# GroundsCoupling.net
KiCad netlist of a schematic drawn in Altium Designer
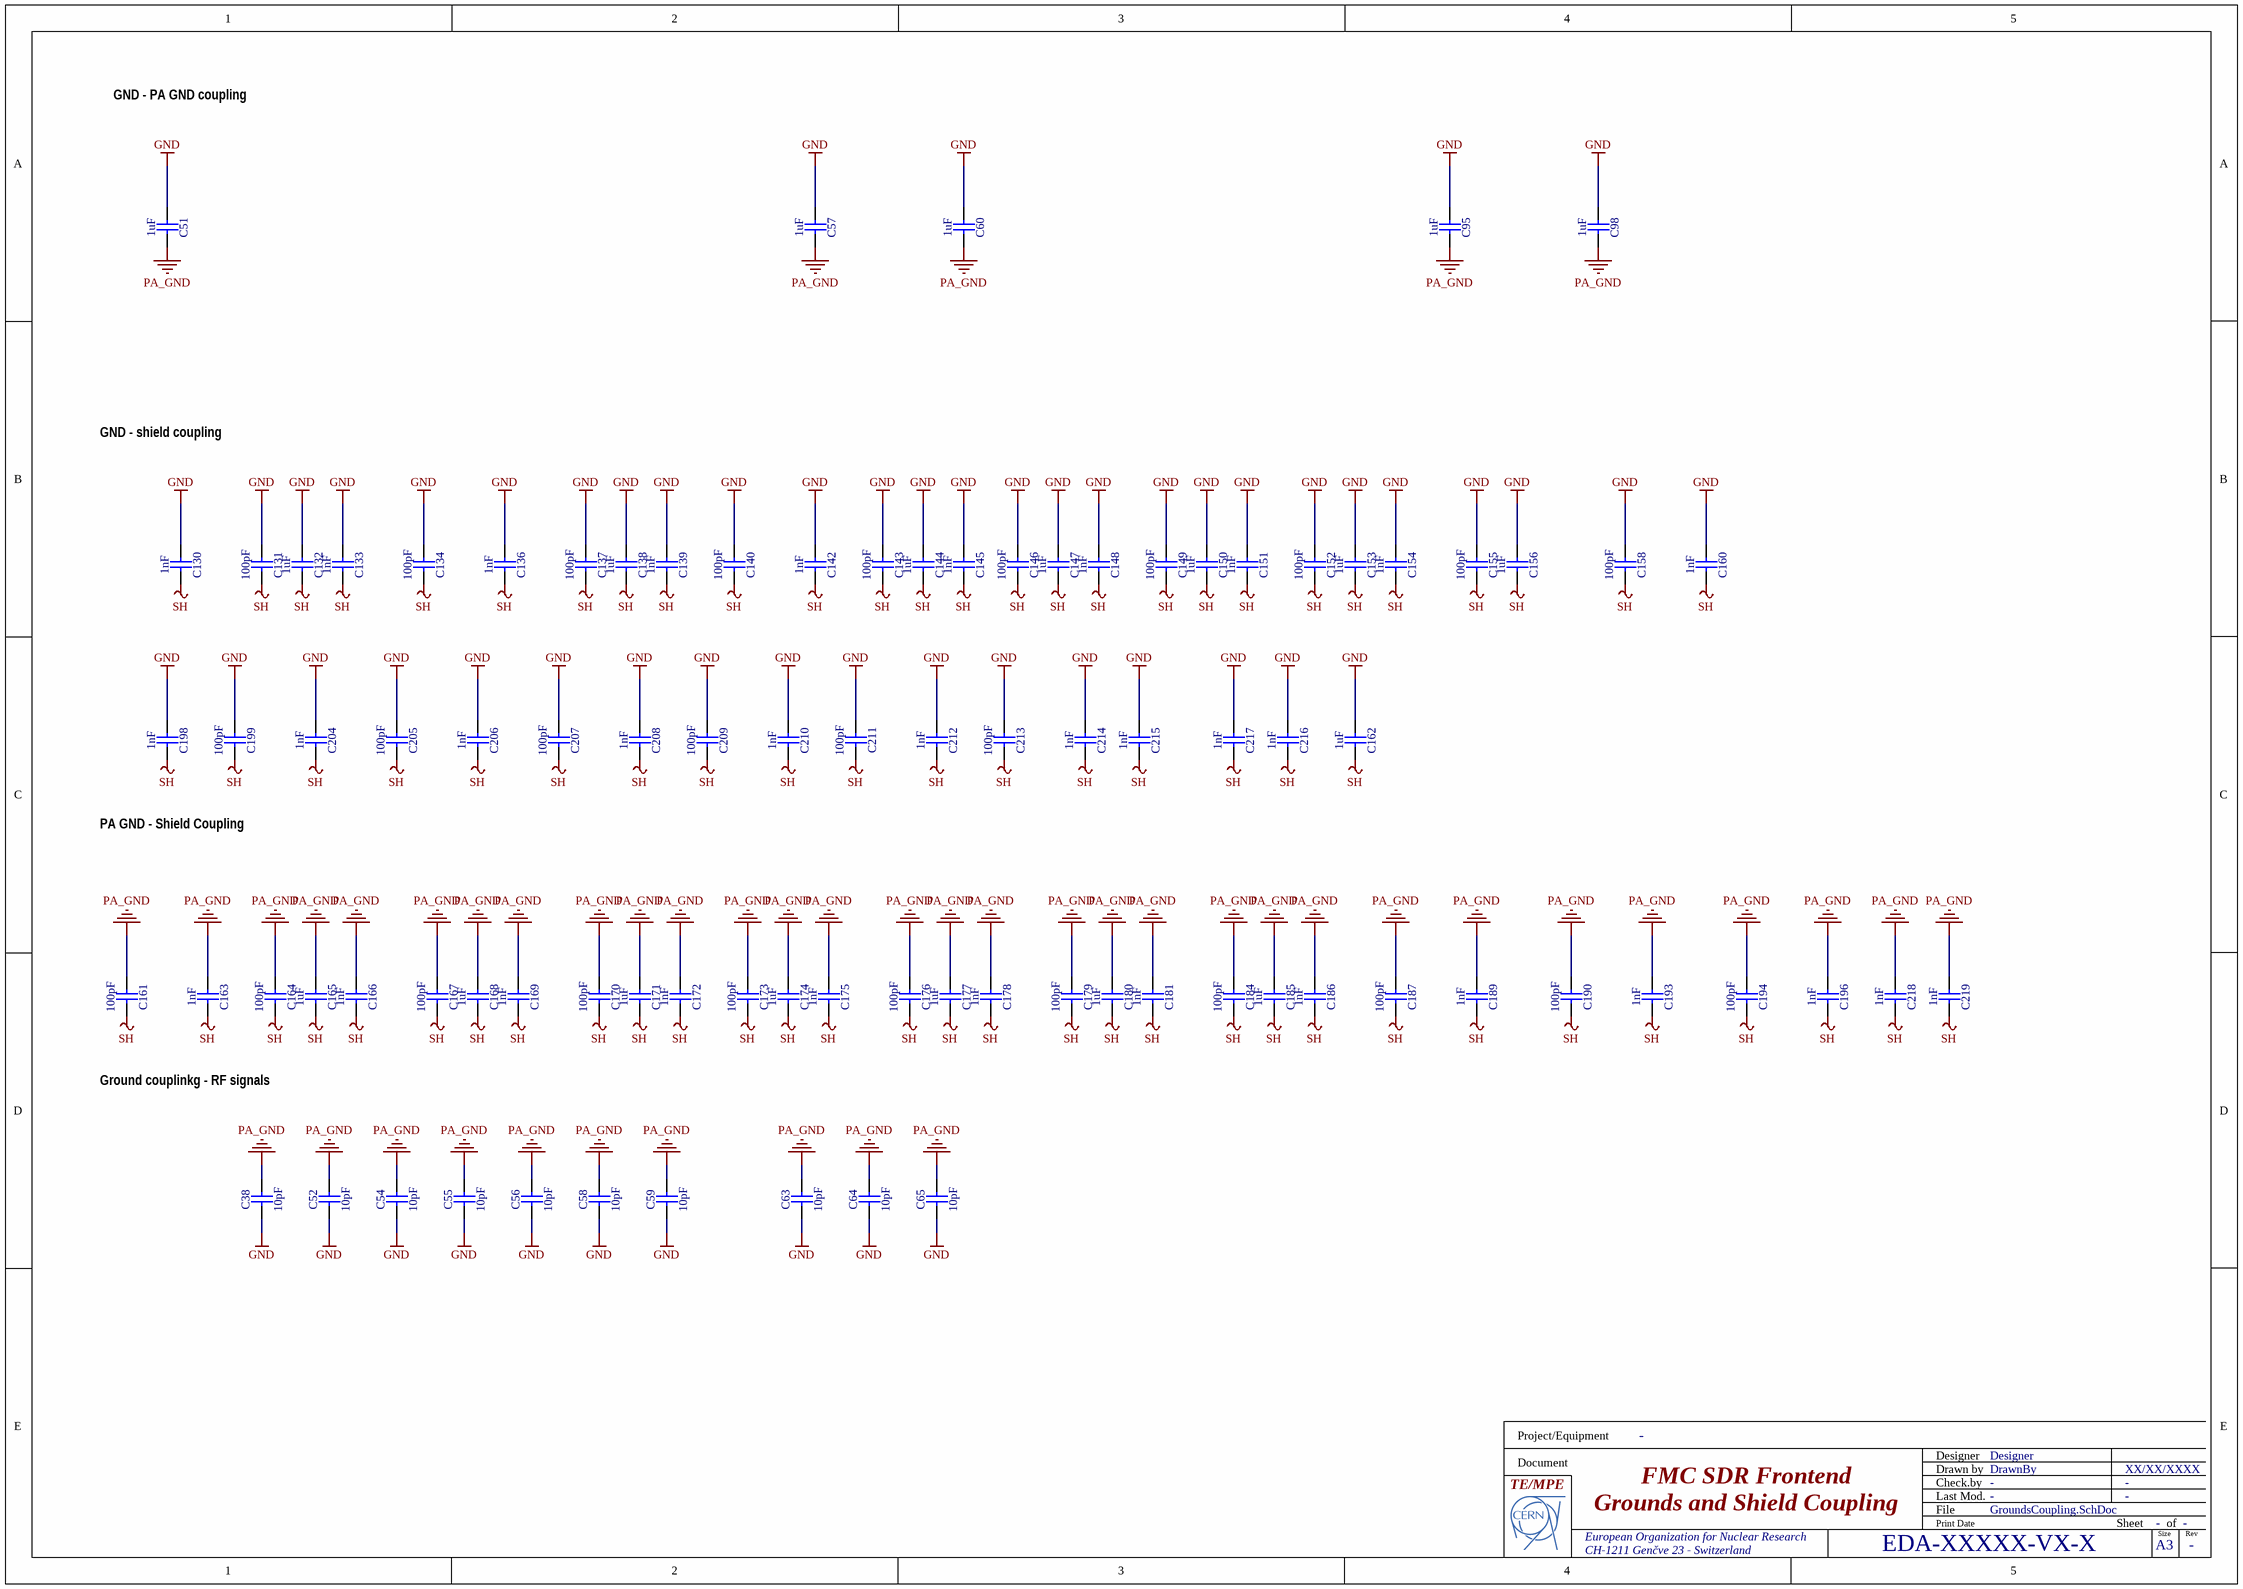
[diagram p0: GroundsCoupling.SchDoc]

(export (version "E")
  (design (tool "Eeschema 10.0.6"))
  (components
    (comp (ref "C38")
      (value "10pF")
      (footprint "CAPC1005X55N")
      (description "Non-polarised capacitor")
      (fields
        (field (name "PART NUMBER") "CC0402_10PF_50V_0.5PF_C0G_YUDEN_UMK105CG100DVHF")
        (field (name "VOLTAGE") "50V")
        (field (name "AUTHOR") "CERN DEM JLC")
      )
      (libsource (lib "Capacitors") (part "Capacitor - non polarized"))
    )
    (comp (ref "C51")
      (value "1uF")
      (footprint "CAPC3216X140N")
      (description "Non-polarised capacitor")
      (fields
        (field (name "PART NUMBER") "CC1206_1UF_50V_10%_X7R")
        (field (name "VOLTAGE") "50V")
        (field (name "AUTHOR") "CERN DEM JLC")
      )
      (libsource (lib "Capacitors") (part "Capacitor - non polarized"))
    )
    (comp (ref "C52")
      (value "10pF")
      (footprint "CAPC1005X55N")
      (description "Non-polarised capacitor")
      (fields
        (field (name "PART NUMBER") "CC0402_10PF_50V_0.5PF_C0G_YUDEN_UMK105CG100DVHF")
        (field (name "VOLTAGE") "50V")
        (field (name "AUTHOR") "CERN DEM JLC")
      )
      (libsource (lib "Capacitors") (part "Capacitor - non polarized"))
    )
    (comp (ref "C54")
      (value "10pF")
      (footprint "CAPC1005X55N")
      (description "Non-polarised capacitor")
      (fields
        (field (name "PART NUMBER") "CC0402_10PF_50V_0.5PF_C0G_YUDEN_UMK105CG100DVHF")
        (field (name "VOLTAGE") "50V")
        (field (name "AUTHOR") "CERN DEM JLC")
      )
      (libsource (lib "Capacitors") (part "Capacitor - non polarized"))
    )
    (comp (ref "C55")
      (value "10pF")
      (footprint "CAPC1005X55N")
      (description "Non-polarised capacitor")
      (fields
        (field (name "PART NUMBER") "CC0402_10PF_50V_0.5PF_C0G_YUDEN_UMK105CG100DVHF")
        (field (name "VOLTAGE") "50V")
        (field (name "AUTHOR") "CERN DEM JLC")
      )
      (libsource (lib "Capacitors") (part "Capacitor - non polarized"))
    )
    (comp (ref "C56")
      (value "10pF")
      (footprint "CAPC1005X55N")
      (description "Non-polarised capacitor")
      (fields
        (field (name "PART NUMBER") "CC0402_10PF_50V_0.5PF_C0G_YUDEN_UMK105CG100DVHF")
        (field (name "VOLTAGE") "50V")
        (field (name "AUTHOR") "CERN DEM JLC")
      )
      (libsource (lib "Capacitors") (part "Capacitor - non polarized"))
    )
    (comp (ref "C57")
      (value "1uF")
      (footprint "CAPC3216X140N")
      (description "Non-polarised capacitor")
      (fields
        (field (name "PART NUMBER") "CC1206_1UF_50V_10%_X7R")
        (field (name "VOLTAGE") "50V")
        (field (name "AUTHOR") "CERN DEM JLC")
      )
      (libsource (lib "Capacitors") (part "Capacitor - non polarized"))
    )
    (comp (ref "C58")
      (value "10pF")
      (footprint "CAPC1005X55N")
      (description "Non-polarised capacitor")
      (fields
        (field (name "PART NUMBER") "CC0402_10PF_50V_0.5PF_C0G_YUDEN_UMK105CG100DVHF")
        (field (name "VOLTAGE") "50V")
        (field (name "AUTHOR") "CERN DEM JLC")
      )
      (libsource (lib "Capacitors") (part "Capacitor - non polarized"))
    )
    (comp (ref "C59")
      (value "10pF")
      (footprint "CAPC1005X55N")
      (description "Non-polarised capacitor")
      (fields
        (field (name "PART NUMBER") "CC0402_10PF_50V_0.5PF_C0G_YUDEN_UMK105CG100DVHF")
        (field (name "VOLTAGE") "50V")
        (field (name "AUTHOR") "CERN DEM JLC")
      )
      (libsource (lib "Capacitors") (part "Capacitor - non polarized"))
    )
    (comp (ref "C60")
      (value "1uF")
      (footprint "CAPC3216X140N")
      (description "Non-polarised capacitor")
      (fields
        (field (name "PART NUMBER") "CC1206_1UF_50V_10%_X7R")
        (field (name "VOLTAGE") "50V")
        (field (name "AUTHOR") "CERN DEM JLC")
      )
      (libsource (lib "Capacitors") (part "Capacitor - non polarized"))
    )
    (comp (ref "C63")
      (value "10pF")
      (footprint "CAPC1005X55N")
      (description "Non-polarised capacitor")
      (fields
        (field (name "PART NUMBER") "CC0402_10PF_50V_0.5PF_C0G_YUDEN_UMK105CG100DVHF")
        (field (name "VOLTAGE") "50V")
        (field (name "AUTHOR") "CERN DEM JLC")
      )
      (libsource (lib "Capacitors") (part "Capacitor - non polarized"))
    )
    (comp (ref "C64")
      (value "10pF")
      (footprint "CAPC1005X55N")
      (description "Non-polarised capacitor")
      (fields
        (field (name "PART NUMBER") "CC0402_10PF_50V_0.5PF_C0G_YUDEN_UMK105CG100DVHF")
        (field (name "VOLTAGE") "50V")
        (field (name "AUTHOR") "CERN DEM JLC")
      )
      (libsource (lib "Capacitors") (part "Capacitor - non polarized"))
    )
    (comp (ref "C65")
      (value "10pF")
      (footprint "CAPC1005X55N")
      (description "Non-polarised capacitor")
      (fields
        (field (name "PART NUMBER") "CC0402_10PF_50V_0.5PF_C0G_YUDEN_UMK105CG100DVHF")
        (field (name "VOLTAGE") "50V")
        (field (name "AUTHOR") "CERN DEM JLC")
      )
      (libsource (lib "Capacitors") (part "Capacitor - non polarized"))
    )
    (comp (ref "C95")
      (value "1uF")
      (footprint "CAPC3216X140N")
      (description "Non-polarised capacitor")
      (fields
        (field (name "PART NUMBER") "CC1206_1UF_50V_10%_X7R")
        (field (name "VOLTAGE") "50V")
        (field (name "AUTHOR") "CERN DEM JLC")
      )
      (libsource (lib "Capacitors") (part "Capacitor - non polarized"))
    )
    (comp (ref "C98")
      (value "1uF")
      (footprint "CAPC3216X140N")
      (description "Non-polarised capacitor")
      (fields
        (field (name "PART NUMBER") "CC1206_1UF_50V_10%_X7R")
        (field (name "VOLTAGE") "50V")
        (field (name "AUTHOR") "CERN DEM JLC")
      )
      (libsource (lib "Capacitors") (part "Capacitor - non polarized"))
    )
    (comp (ref "C130")
      (value "1nF")
      (footprint "CAPC1005X55N")
      (description "Non-polarised capacitor")
      (fields
        (field (name "PART NUMBER") "CC0402_1NF_50V_10%_X7R")
        (field (name "VOLTAGE") "50V")
        (field (name "AUTHOR") "CERN DEM JLC")
      )
      (libsource (lib "Capacitors") (part "Capacitor - non polarized"))
    )
    (comp (ref "C131")
      (value "100pF")
      (footprint "CAPC1005X55N")
      (description "Non-polarised capacitor")
      (fields
        (field (name "PART NUMBER") "CC0402_100PF_50V_5%_C0G")
        (field (name "VOLTAGE") "50V")
        (field (name "AUTHOR") "CERN DEM JLC")
      )
      (libsource (lib "Capacitors") (part "Capacitor - non polarized"))
    )
    (comp (ref "C132")
      (value "1uF")
      (footprint "CAPC3216X140N")
      (description "Non-polarised capacitor")
      (fields
        (field (name "PART NUMBER") "CC1206_1UF_50V_10%_X7R")
        (field (name "VOLTAGE") "50V")
        (field (name "AUTHOR") "CERN DEM JLC")
      )
      (libsource (lib "Capacitors") (part "Capacitor - non polarized"))
    )
    (comp (ref "C133")
      (value "1nF")
      (footprint "CAPC1005X55N")
      (description "Non-polarised capacitor")
      (fields
        (field (name "PART NUMBER") "CC0402_1NF_50V_10%_X7R")
        (field (name "VOLTAGE") "50V")
        (field (name "AUTHOR") "CERN DEM JLC")
      )
      (libsource (lib "Capacitors") (part "Capacitor - non polarized"))
    )
    (comp (ref "C134")
      (value "100pF")
      (footprint "CAPC1005X55N")
      (description "Non-polarised capacitor")
      (fields
        (field (name "PART NUMBER") "CC0402_100PF_50V_5%_C0G")
        (field (name "VOLTAGE") "50V")
        (field (name "AUTHOR") "CERN DEM JLC")
      )
      (libsource (lib "Capacitors") (part "Capacitor - non polarized"))
    )
    (comp (ref "C136")
      (value "1nF")
      (footprint "CAPC1005X55N")
      (description "Non-polarised capacitor")
      (fields
        (field (name "PART NUMBER") "CC0402_1NF_50V_10%_X7R")
        (field (name "VOLTAGE") "50V")
        (field (name "AUTHOR") "CERN DEM JLC")
      )
      (libsource (lib "Capacitors") (part "Capacitor - non polarized"))
    )
    (comp (ref "C137")
      (value "100pF")
      (footprint "CAPC1005X55N")
      (description "Non-polarised capacitor")
      (fields
        (field (name "PART NUMBER") "CC0402_100PF_50V_5%_C0G")
        (field (name "VOLTAGE") "50V")
        (field (name "AUTHOR") "CERN DEM JLC")
      )
      (libsource (lib "Capacitors") (part "Capacitor - non polarized"))
    )
    (comp (ref "C138")
      (value "1uF")
      (footprint "CAPC3216X140N")
      (description "Non-polarised capacitor")
      (fields
        (field (name "PART NUMBER") "CC1206_1UF_50V_10%_X7R")
        (field (name "VOLTAGE") "50V")
        (field (name "AUTHOR") "CERN DEM JLC")
      )
      (libsource (lib "Capacitors") (part "Capacitor - non polarized"))
    )
    (comp (ref "C139")
      (value "1nF")
      (footprint "CAPC1005X55N")
      (description "Non-polarised capacitor")
      (fields
        (field (name "PART NUMBER") "CC0402_1NF_50V_10%_X7R")
        (field (name "VOLTAGE") "50V")
        (field (name "AUTHOR") "CERN DEM JLC")
      )
      (libsource (lib "Capacitors") (part "Capacitor - non polarized"))
    )
    (comp (ref "C140")
      (value "100pF")
      (footprint "CAPC1005X55N")
      (description "Non-polarised capacitor")
      (fields
        (field (name "PART NUMBER") "CC0402_100PF_50V_5%_C0G")
        (field (name "VOLTAGE") "50V")
        (field (name "AUTHOR") "CERN DEM JLC")
      )
      (libsource (lib "Capacitors") (part "Capacitor - non polarized"))
    )
    (comp (ref "C142")
      (value "1nF")
      (footprint "CAPC1005X55N")
      (description "Non-polarised capacitor")
      (fields
        (field (name "PART NUMBER") "CC0402_1NF_50V_10%_X7R")
        (field (name "VOLTAGE") "50V")
        (field (name "AUTHOR") "CERN DEM JLC")
      )
      (libsource (lib "Capacitors") (part "Capacitor - non polarized"))
    )
    (comp (ref "C143")
      (value "100pF")
      (footprint "CAPC1005X55N")
      (description "Non-polarised capacitor")
      (fields
        (field (name "PART NUMBER") "CC0402_100PF_50V_5%_C0G")
        (field (name "VOLTAGE") "50V")
        (field (name "AUTHOR") "CERN DEM JLC")
      )
      (libsource (lib "Capacitors") (part "Capacitor - non polarized"))
    )
    (comp (ref "C144")
      (value "1uF")
      (footprint "CAPC3216X140N")
      (description "Non-polarised capacitor")
      (fields
        (field (name "PART NUMBER") "CC1206_1UF_50V_10%_X7R")
        (field (name "VOLTAGE") "50V")
        (field (name "AUTHOR") "CERN DEM JLC")
      )
      (libsource (lib "Capacitors") (part "Capacitor - non polarized"))
    )
    (comp (ref "C145")
      (value "1nF")
      (footprint "CAPC1005X55N")
      (description "Non-polarised capacitor")
      (fields
        (field (name "PART NUMBER") "CC0402_1NF_50V_10%_X7R")
        (field (name "VOLTAGE") "50V")
        (field (name "AUTHOR") "CERN DEM JLC")
      )
      (libsource (lib "Capacitors") (part "Capacitor - non polarized"))
    )
    (comp (ref "C146")
      (value "100pF")
      (footprint "CAPC1005X55N")
      (description "Non-polarised capacitor")
      (fields
        (field (name "PART NUMBER") "CC0402_100PF_50V_5%_C0G")
        (field (name "VOLTAGE") "50V")
        (field (name "AUTHOR") "CERN DEM JLC")
      )
      (libsource (lib "Capacitors") (part "Capacitor - non polarized"))
    )
    (comp (ref "C147")
      (value "1uF")
      (footprint "CAPC3216X140N")
      (description "Non-polarised capacitor")
      (fields
        (field (name "PART NUMBER") "CC1206_1UF_50V_10%_X7R")
        (field (name "VOLTAGE") "50V")
        (field (name "AUTHOR") "CERN DEM JLC")
      )
      (libsource (lib "Capacitors") (part "Capacitor - non polarized"))
    )
    (comp (ref "C148")
      (value "1nF")
      (footprint "CAPC1005X55N")
      (description "Non-polarised capacitor")
      (fields
        (field (name "PART NUMBER") "CC0402_1NF_50V_10%_X7R")
        (field (name "VOLTAGE") "50V")
        (field (name "AUTHOR") "CERN DEM JLC")
      )
      (libsource (lib "Capacitors") (part "Capacitor - non polarized"))
    )
    (comp (ref "C149")
      (value "100pF")
      (footprint "CAPC1005X55N")
      (description "Non-polarised capacitor")
      (fields
        (field (name "PART NUMBER") "CC0402_100PF_50V_5%_C0G")
        (field (name "VOLTAGE") "50V")
        (field (name "AUTHOR") "CERN DEM JLC")
      )
      (libsource (lib "Capacitors") (part "Capacitor - non polarized"))
    )
    (comp (ref "C150")
      (value "1uF")
      (footprint "CAPC3216X140N")
      (description "Non-polarised capacitor")
      (fields
        (field (name "PART NUMBER") "CC1206_1UF_50V_10%_X7R")
        (field (name "VOLTAGE") "50V")
        (field (name "AUTHOR") "CERN DEM JLC")
      )
      (libsource (lib "Capacitors") (part "Capacitor - non polarized"))
    )
    (comp (ref "C151")
      (value "1nF")
      (footprint "CAPC1005X55N")
      (description "Non-polarised capacitor")
      (fields
        (field (name "PART NUMBER") "CC0402_1NF_50V_10%_X7R")
        (field (name "VOLTAGE") "50V")
        (field (name "AUTHOR") "CERN DEM JLC")
      )
      (libsource (lib "Capacitors") (part "Capacitor - non polarized"))
    )
    (comp (ref "C152")
      (value "100pF")
      (footprint "CAPC1005X55N")
      (description "Non-polarised capacitor")
      (fields
        (field (name "PART NUMBER") "CC0402_100PF_50V_5%_C0G")
        (field (name "VOLTAGE") "50V")
        (field (name "AUTHOR") "CERN DEM JLC")
      )
      (libsource (lib "Capacitors") (part "Capacitor - non polarized"))
    )
    (comp (ref "C153")
      (value "1uF")
      (footprint "CAPC3216X140N")
      (description "Non-polarised capacitor")
      (fields
        (field (name "PART NUMBER") "CC1206_1UF_50V_10%_X7R")
        (field (name "VOLTAGE") "50V")
        (field (name "AUTHOR") "CERN DEM JLC")
      )
      (libsource (lib "Capacitors") (part "Capacitor - non polarized"))
    )
    (comp (ref "C154")
      (value "1nF")
      (footprint "CAPC1005X55N")
      (description "Non-polarised capacitor")
      (fields
        (field (name "PART NUMBER") "CC0402_1NF_50V_10%_X7R")
        (field (name "VOLTAGE") "50V")
        (field (name "AUTHOR") "CERN DEM JLC")
      )
      (libsource (lib "Capacitors") (part "Capacitor - non polarized"))
    )
    (comp (ref "C155")
      (value "100pF")
      (footprint "CAPC1005X55N")
      (description "Non-polarised capacitor")
      (fields
        (field (name "PART NUMBER") "CC0402_100PF_50V_5%_C0G")
        (field (name "VOLTAGE") "50V")
        (field (name "AUTHOR") "CERN DEM JLC")
      )
      (libsource (lib "Capacitors") (part "Capacitor - non polarized"))
    )
    (comp (ref "C156")
      (value "1uF")
      (footprint "CAPC3216X140N")
      (description "Non-polarised capacitor")
      (fields
        (field (name "PART NUMBER") "CC1206_1UF_50V_10%_X7R")
        (field (name "VOLTAGE") "50V")
        (field (name "AUTHOR") "CERN DEM JLC")
      )
      (libsource (lib "Capacitors") (part "Capacitor - non polarized"))
    )
    (comp (ref "C158")
      (value "100pF")
      (footprint "CAPC1005X55N")
      (description "Non-polarised capacitor")
      (fields
        (field (name "PART NUMBER") "CC0402_100PF_50V_5%_C0G")
        (field (name "VOLTAGE") "50V")
        (field (name "AUTHOR") "CERN DEM JLC")
      )
      (libsource (lib "Capacitors") (part "Capacitor - non polarized"))
    )
    (comp (ref "C160")
      (value "1nF")
      (footprint "CAPC1005X55N")
      (description "Non-polarised capacitor")
      (fields
        (field (name "PART NUMBER") "CC0402_1NF_50V_10%_X7R")
        (field (name "VOLTAGE") "50V")
        (field (name "AUTHOR") "CERN DEM JLC")
      )
      (libsource (lib "Capacitors") (part "Capacitor - non polarized"))
    )
    (comp (ref "C161")
      (value "100pF")
      (footprint "CAPC1005X55N")
      (description "Non-polarised capacitor")
      (fields
        (field (name "PART NUMBER") "CC0402_100PF_50V_5%_C0G")
        (field (name "VOLTAGE") "50V")
        (field (name "AUTHOR") "CERN DEM JLC")
      )
      (libsource (lib "Capacitors") (part "Capacitor - non polarized"))
    )
    (comp (ref "C162")
      (value "1uF")
      (footprint "CAPC3216X140N")
      (description "Non-polarised capacitor")
      (fields
        (field (name "PART NUMBER") "CC1206_1UF_50V_10%_X7R")
        (field (name "VOLTAGE") "50V")
        (field (name "AUTHOR") "CERN DEM JLC")
      )
      (libsource (lib "Capacitors") (part "Capacitor - non polarized"))
    )
    (comp (ref "C163")
      (value "1nF")
      (footprint "CAPC1005X55N")
      (description "Non-polarised capacitor")
      (fields
        (field (name "PART NUMBER") "CC0402_1NF_50V_10%_X7R")
        (field (name "VOLTAGE") "50V")
        (field (name "AUTHOR") "CERN DEM JLC")
      )
      (libsource (lib "Capacitors") (part "Capacitor - non polarized"))
    )
    (comp (ref "C164")
      (value "100pF")
      (footprint "CAPC1005X55N")
      (description "Non-polarised capacitor")
      (fields
        (field (name "PART NUMBER") "CC0402_100PF_50V_5%_C0G")
        (field (name "VOLTAGE") "50V")
        (field (name "AUTHOR") "CERN DEM JLC")
      )
      (libsource (lib "Capacitors") (part "Capacitor - non polarized"))
    )
    (comp (ref "C165")
      (value "1uF")
      (footprint "CAPC3216X140N")
      (description "Non-polarised capacitor")
      (fields
        (field (name "PART NUMBER") "CC1206_1UF_50V_10%_X7R")
        (field (name "VOLTAGE") "50V")
        (field (name "AUTHOR") "CERN DEM JLC")
      )
      (libsource (lib "Capacitors") (part "Capacitor - non polarized"))
    )
    (comp (ref "C166")
      (value "1nF")
      (footprint "CAPC1005X55N")
      (description "Non-polarised capacitor")
      (fields
        (field (name "PART NUMBER") "CC0402_1NF_50V_10%_X7R")
        (field (name "VOLTAGE") "50V")
        (field (name "AUTHOR") "CERN DEM JLC")
      )
      (libsource (lib "Capacitors") (part "Capacitor - non polarized"))
    )
    (comp (ref "C167")
      (value "100pF")
      (footprint "CAPC1005X55N")
      (description "Non-polarised capacitor")
      (fields
        (field (name "PART NUMBER") "CC0402_100PF_50V_5%_C0G")
        (field (name "VOLTAGE") "50V")
        (field (name "AUTHOR") "CERN DEM JLC")
      )
      (libsource (lib "Capacitors") (part "Capacitor - non polarized"))
    )
    (comp (ref "C168")
      (value "1uF")
      (footprint "CAPC3216X140N")
      (description "Non-polarised capacitor")
      (fields
        (field (name "PART NUMBER") "CC1206_1UF_50V_10%_X7R")
        (field (name "VOLTAGE") "50V")
        (field (name "AUTHOR") "CERN DEM JLC")
      )
      (libsource (lib "Capacitors") (part "Capacitor - non polarized"))
    )
    (comp (ref "C169")
      (value "1nF")
      (footprint "CAPC1005X55N")
      (description "Non-polarised capacitor")
      (fields
        (field (name "PART NUMBER") "CC0402_1NF_50V_10%_X7R")
        (field (name "VOLTAGE") "50V")
        (field (name "AUTHOR") "CERN DEM JLC")
      )
      (libsource (lib "Capacitors") (part "Capacitor - non polarized"))
    )
    (comp (ref "C170")
      (value "100pF")
      (footprint "CAPC1005X55N")
      (description "Non-polarised capacitor")
      (fields
        (field (name "PART NUMBER") "CC0402_100PF_50V_5%_C0G")
        (field (name "VOLTAGE") "50V")
        (field (name "AUTHOR") "CERN DEM JLC")
      )
      (libsource (lib "Capacitors") (part "Capacitor - non polarized"))
    )
    (comp (ref "C171")
      (value "1uF")
      (footprint "CAPC3216X140N")
      (description "Non-polarised capacitor")
      (fields
        (field (name "PART NUMBER") "CC1206_1UF_50V_10%_X7R")
        (field (name "VOLTAGE") "50V")
        (field (name "AUTHOR") "CERN DEM JLC")
      )
      (libsource (lib "Capacitors") (part "Capacitor - non polarized"))
    )
    (comp (ref "C172")
      (value "1nF")
      (footprint "CAPC1005X55N")
      (description "Non-polarised capacitor")
      (fields
        (field (name "PART NUMBER") "CC0402_1NF_50V_10%_X7R")
        (field (name "VOLTAGE") "50V")
        (field (name "AUTHOR") "CERN DEM JLC")
      )
      (libsource (lib "Capacitors") (part "Capacitor - non polarized"))
    )
    (comp (ref "C173")
      (value "100pF")
      (footprint "CAPC1005X55N")
      (description "Non-polarised capacitor")
      (fields
        (field (name "PART NUMBER") "CC0402_100PF_50V_5%_C0G")
        (field (name "VOLTAGE") "50V")
        (field (name "AUTHOR") "CERN DEM JLC")
      )
      (libsource (lib "Capacitors") (part "Capacitor - non polarized"))
    )
    (comp (ref "C174")
      (value "1uF")
      (footprint "CAPC3216X140N")
      (description "Non-polarised capacitor")
      (fields
        (field (name "PART NUMBER") "CC1206_1UF_50V_10%_X7R")
        (field (name "VOLTAGE") "50V")
        (field (name "AUTHOR") "CERN DEM JLC")
      )
      (libsource (lib "Capacitors") (part "Capacitor - non polarized"))
    )
    (comp (ref "C175")
      (value "1nF")
      (footprint "CAPC1005X55N")
      (description "Non-polarised capacitor")
      (fields
        (field (name "PART NUMBER") "CC0402_1NF_50V_10%_X7R")
        (field (name "VOLTAGE") "50V")
        (field (name "AUTHOR") "CERN DEM JLC")
      )
      (libsource (lib "Capacitors") (part "Capacitor - non polarized"))
    )
    (comp (ref "C176")
      (value "100pF")
      (footprint "CAPC1005X55N")
      (description "Non-polarised capacitor")
      (fields
        (field (name "PART NUMBER") "CC0402_100PF_50V_5%_C0G")
        (field (name "VOLTAGE") "50V")
        (field (name "AUTHOR") "CERN DEM JLC")
      )
      (libsource (lib "Capacitors") (part "Capacitor - non polarized"))
    )
    (comp (ref "C177")
      (value "1uF")
      (footprint "CAPC3216X140N")
      (description "Non-polarised capacitor")
      (fields
        (field (name "PART NUMBER") "CC1206_1UF_50V_10%_X7R")
        (field (name "VOLTAGE") "50V")
        (field (name "AUTHOR") "CERN DEM JLC")
      )
      (libsource (lib "Capacitors") (part "Capacitor - non polarized"))
    )
    (comp (ref "C178")
      (value "1nF")
      (footprint "CAPC1005X55N")
      (description "Non-polarised capacitor")
      (fields
        (field (name "PART NUMBER") "CC0402_1NF_50V_10%_X7R")
        (field (name "VOLTAGE") "50V")
        (field (name "AUTHOR") "CERN DEM JLC")
      )
      (libsource (lib "Capacitors") (part "Capacitor - non polarized"))
    )
    (comp (ref "C179")
      (value "100pF")
      (footprint "CAPC1005X55N")
      (description "Non-polarised capacitor")
      (fields
        (field (name "PART NUMBER") "CC0402_100PF_50V_5%_C0G")
        (field (name "VOLTAGE") "50V")
        (field (name "AUTHOR") "CERN DEM JLC")
      )
      (libsource (lib "Capacitors") (part "Capacitor - non polarized"))
    )
    (comp (ref "C180")
      (value "1uF")
      (footprint "CAPC3216X140N")
      (description "Non-polarised capacitor")
      (fields
        (field (name "PART NUMBER") "CC1206_1UF_50V_10%_X7R")
        (field (name "VOLTAGE") "50V")
        (field (name "AUTHOR") "CERN DEM JLC")
      )
      (libsource (lib "Capacitors") (part "Capacitor - non polarized"))
    )
    (comp (ref "C181")
      (value "1nF")
      (footprint "CAPC1005X55N")
      (description "Non-polarised capacitor")
      (fields
        (field (name "PART NUMBER") "CC0402_1NF_50V_10%_X7R")
        (field (name "VOLTAGE") "50V")
        (field (name "AUTHOR") "CERN DEM JLC")
      )
      (libsource (lib "Capacitors") (part "Capacitor - non polarized"))
    )
    (comp (ref "C184")
      (value "100pF")
      (footprint "CAPC1005X55N")
      (description "Non-polarised capacitor")
      (fields
        (field (name "PART NUMBER") "CC0402_100PF_50V_5%_C0G")
        (field (name "VOLTAGE") "50V")
        (field (name "AUTHOR") "CERN DEM JLC")
      )
      (libsource (lib "Capacitors") (part "Capacitor - non polarized"))
    )
    (comp (ref "C185")
      (value "1uF")
      (footprint "CAPC3216X140N")
      (description "Non-polarised capacitor")
      (fields
        (field (name "PART NUMBER") "CC1206_1UF_50V_10%_X7R")
        (field (name "VOLTAGE") "50V")
        (field (name "AUTHOR") "CERN DEM JLC")
      )
      (libsource (lib "Capacitors") (part "Capacitor - non polarized"))
    )
    (comp (ref "C186")
      (value "1nF")
      (footprint "CAPC1005X55N")
      (description "Non-polarised capacitor")
      (fields
        (field (name "PART NUMBER") "CC0402_1NF_50V_10%_X7R")
        (field (name "VOLTAGE") "50V")
        (field (name "AUTHOR") "CERN DEM JLC")
      )
      (libsource (lib "Capacitors") (part "Capacitor - non polarized"))
    )
    (comp (ref "C187")
      (value "100pF")
      (footprint "CAPC1005X55N")
      (description "Non-polarised capacitor")
      (fields
        (field (name "PART NUMBER") "CC0402_100PF_50V_5%_C0G")
        (field (name "VOLTAGE") "50V")
        (field (name "AUTHOR") "CERN DEM JLC")
      )
      (libsource (lib "Capacitors") (part "Capacitor - non polarized"))
    )
    (comp (ref "C189")
      (value "1nF")
      (footprint "CAPC1005X55N")
      (description "Non-polarised capacitor")
      (fields
        (field (name "PART NUMBER") "CC0402_1NF_50V_10%_X7R")
        (field (name "VOLTAGE") "50V")
        (field (name "AUTHOR") "CERN DEM JLC")
      )
      (libsource (lib "Capacitors") (part "Capacitor - non polarized"))
    )
    (comp (ref "C190")
      (value "100pF")
      (footprint "CAPC1005X55N")
      (description "Non-polarised capacitor")
      (fields
        (field (name "PART NUMBER") "CC0402_100PF_50V_5%_C0G")
        (field (name "VOLTAGE") "50V")
        (field (name "AUTHOR") "CERN DEM JLC")
      )
      (libsource (lib "Capacitors") (part "Capacitor - non polarized"))
    )
    (comp (ref "C193")
      (value "1nF")
      (footprint "CAPC1005X55N")
      (description "Non-polarised capacitor")
      (fields
        (field (name "PART NUMBER") "CC0402_1NF_50V_10%_X7R")
        (field (name "VOLTAGE") "50V")
        (field (name "AUTHOR") "CERN DEM JLC")
      )
      (libsource (lib "Capacitors") (part "Capacitor - non polarized"))
    )
    (comp (ref "C194")
      (value "100pF")
      (footprint "CAPC1005X55N")
      (description "Non-polarised capacitor")
      (fields
        (field (name "PART NUMBER") "CC0402_100PF_50V_5%_C0G")
        (field (name "VOLTAGE") "50V")
        (field (name "AUTHOR") "CERN DEM JLC")
      )
      (libsource (lib "Capacitors") (part "Capacitor - non polarized"))
    )
    (comp (ref "C196")
      (value "1nF")
      (footprint "CAPC1005X55N")
      (description "Non-polarised capacitor")
      (fields
        (field (name "PART NUMBER") "CC0402_1NF_50V_10%_X7R")
        (field (name "VOLTAGE") "50V")
        (field (name "AUTHOR") "CERN DEM JLC")
      )
      (libsource (lib "Capacitors") (part "Capacitor - non polarized"))
    )
    (comp (ref "C198")
      (value "1nF")
      (footprint "CAPC1005X55N")
      (description "Non-polarised capacitor")
      (fields
        (field (name "PART NUMBER") "CC0402_1NF_50V_10%_X7R")
        (field (name "VOLTAGE") "50V")
        (field (name "AUTHOR") "CERN DEM JLC")
      )
      (libsource (lib "Capacitors") (part "Capacitor - non polarized"))
    )
    (comp (ref "C199")
      (value "100pF")
      (footprint "CAPC1005X55N")
      (description "Non-polarised capacitor")
      (fields
        (field (name "PART NUMBER") "CC0402_100PF_50V_5%_C0G")
        (field (name "VOLTAGE") "50V")
        (field (name "AUTHOR") "CERN DEM JLC")
      )
      (libsource (lib "Capacitors") (part "Capacitor - non polarized"))
    )
    (comp (ref "C204")
      (value "1nF")
      (footprint "CAPC1005X55N")
      (description "Non-polarised capacitor")
      (fields
        (field (name "PART NUMBER") "CC0402_1NF_50V_10%_X7R")
        (field (name "VOLTAGE") "50V")
        (field (name "AUTHOR") "CERN DEM JLC")
      )
      (libsource (lib "Capacitors") (part "Capacitor - non polarized"))
    )
    (comp (ref "C205")
      (value "100pF")
      (footprint "CAPC1005X55N")
      (description "Non-polarised capacitor")
      (fields
        (field (name "PART NUMBER") "CC0402_100PF_50V_5%_C0G")
        (field (name "VOLTAGE") "50V")
        (field (name "AUTHOR") "CERN DEM JLC")
      )
      (libsource (lib "Capacitors") (part "Capacitor - non polarized"))
    )
    (comp (ref "C206")
      (value "1nF")
      (footprint "CAPC1005X55N")
      (description "Non-polarised capacitor")
      (fields
        (field (name "PART NUMBER") "CC0402_1NF_50V_10%_X7R")
        (field (name "VOLTAGE") "50V")
        (field (name "AUTHOR") "CERN DEM JLC")
      )
      (libsource (lib "Capacitors") (part "Capacitor - non polarized"))
    )
    (comp (ref "C207")
      (value "100pF")
      (footprint "CAPC1005X55N")
      (description "Non-polarised capacitor")
      (fields
        (field (name "PART NUMBER") "CC0402_100PF_50V_5%_C0G")
        (field (name "VOLTAGE") "50V")
        (field (name "AUTHOR") "CERN DEM JLC")
      )
      (libsource (lib "Capacitors") (part "Capacitor - non polarized"))
    )
    (comp (ref "C208")
      (value "1nF")
      (footprint "CAPC1005X55N")
      (description "Non-polarised capacitor")
      (fields
        (field (name "PART NUMBER") "CC0402_1NF_50V_10%_X7R")
        (field (name "VOLTAGE") "50V")
        (field (name "AUTHOR") "CERN DEM JLC")
      )
      (libsource (lib "Capacitors") (part "Capacitor - non polarized"))
    )
    (comp (ref "C209")
      (value "100pF")
      (footprint "CAPC1005X55N")
      (description "Non-polarised capacitor")
      (fields
        (field (name "PART NUMBER") "CC0402_100PF_50V_5%_C0G")
        (field (name "VOLTAGE") "50V")
        (field (name "AUTHOR") "CERN DEM JLC")
      )
      (libsource (lib "Capacitors") (part "Capacitor - non polarized"))
    )
    (comp (ref "C210")
      (value "1nF")
      (footprint "CAPC1005X55N")
      (description "Non-polarised capacitor")
      (fields
        (field (name "PART NUMBER") "CC0402_1NF_50V_10%_X7R")
        (field (name "VOLTAGE") "50V")
        (field (name "AUTHOR") "CERN DEM JLC")
      )
      (libsource (lib "Capacitors") (part "Capacitor - non polarized"))
    )
    (comp (ref "C211")
      (value "100pF")
      (footprint "CAPC1005X55N")
      (description "Non-polarised capacitor")
      (fields
        (field (name "PART NUMBER") "CC0402_100PF_50V_5%_C0G")
        (field (name "VOLTAGE") "50V")
        (field (name "AUTHOR") "CERN DEM JLC")
      )
      (libsource (lib "Capacitors") (part "Capacitor - non polarized"))
    )
    (comp (ref "C212")
      (value "1nF")
      (footprint "CAPC1005X55N")
      (description "Non-polarised capacitor")
      (fields
        (field (name "PART NUMBER") "CC0402_1NF_50V_10%_X7R")
        (field (name "VOLTAGE") "50V")
        (field (name "AUTHOR") "CERN DEM JLC")
      )
      (libsource (lib "Capacitors") (part "Capacitor - non polarized"))
    )
    (comp (ref "C213")
      (value "100pF")
      (footprint "CAPC1005X55N")
      (description "Non-polarised capacitor")
      (fields
        (field (name "PART NUMBER") "CC0402_100PF_50V_5%_C0G")
        (field (name "VOLTAGE") "50V")
        (field (name "AUTHOR") "CERN DEM JLC")
      )
      (libsource (lib "Capacitors") (part "Capacitor - non polarized"))
    )
    (comp (ref "C214")
      (value "1nF")
      (footprint "CAPC1005X55N")
      (description "Non-polarised capacitor")
      (fields
        (field (name "PART NUMBER") "CC0402_1NF_50V_10%_X7R")
        (field (name "VOLTAGE") "50V")
        (field (name "AUTHOR") "CERN DEM JLC")
      )
      (libsource (lib "Capacitors") (part "Capacitor - non polarized"))
    )
    (comp (ref "C215")
      (value "1nF")
      (footprint "CAPC1005X55N")
      (description "Non-polarised capacitor")
      (fields
        (field (name "PART NUMBER") "CC0402_1NF_50V_10%_X7R")
        (field (name "VOLTAGE") "50V")
        (field (name "AUTHOR") "CERN DEM JLC")
      )
      (libsource (lib "Capacitors") (part "Capacitor - non polarized"))
    )
    (comp (ref "C216")
      (value "1nF")
      (footprint "CAPC1005X55N")
      (description "Non-polarised capacitor")
      (fields
        (field (name "PART NUMBER") "CC0402_1NF_50V_10%_X7R")
        (field (name "VOLTAGE") "50V")
        (field (name "AUTHOR") "CERN DEM JLC")
      )
      (libsource (lib "Capacitors") (part "Capacitor - non polarized"))
    )
    (comp (ref "C217")
      (value "1nF")
      (footprint "CAPC1005X55N")
      (description "Non-polarised capacitor")
      (fields
        (field (name "PART NUMBER") "CC0402_1NF_50V_10%_X7R")
        (field (name "VOLTAGE") "50V")
        (field (name "AUTHOR") "CERN DEM JLC")
      )
      (libsource (lib "Capacitors") (part "Capacitor - non polarized"))
    )
    (comp (ref "C218")
      (value "1nF")
      (footprint "CAPC1005X55N")
      (description "Non-polarised capacitor")
      (fields
        (field (name "PART NUMBER") "CC0402_1NF_50V_10%_X7R")
        (field (name "VOLTAGE") "50V")
        (field (name "AUTHOR") "CERN DEM JLC")
      )
      (libsource (lib "Capacitors") (part "Capacitor - non polarized"))
    )
    (comp (ref "C219")
      (value "1nF")
      (footprint "CAPC1005X55N")
      (description "Non-polarised capacitor")
      (fields
        (field (name "PART NUMBER") "CC0402_1NF_50V_10%_X7R")
        (field (name "VOLTAGE") "50V")
        (field (name "AUTHOR") "CERN DEM JLC")
      )
      (libsource (lib "Capacitors") (part "Capacitor - non polarized"))
    )
  )
  (nets
    (net (code "1") (name "GND") (class "Default")
      (node (ref "C130") (pin "1") (pinfunction "1_1") (pintype "passive"))
      (node (ref "C131") (pin "1") (pinfunction "1_1") (pintype "passive"))
      (node (ref "C132") (pin "1") (pinfunction "1_1") (pintype "passive"))
      (node (ref "C133") (pin "1") (pinfunction "1_1") (pintype "passive"))
      (node (ref "C134") (pin "1") (pinfunction "1_1") (pintype "passive"))
      (node (ref "C136") (pin "1") (pinfunction "1_1") (pintype "passive"))
      (node (ref "C137") (pin "1") (pinfunction "1_1") (pintype "passive"))
      (node (ref "C138") (pin "1") (pinfunction "1_1") (pintype "passive"))
      (node (ref "C139") (pin "1") (pinfunction "1_1") (pintype "passive"))
      (node (ref "C140") (pin "1") (pinfunction "1_1") (pintype "passive"))
      (node (ref "C142") (pin "1") (pinfunction "1_1") (pintype "passive"))
      (node (ref "C143") (pin "1") (pinfunction "1_1") (pintype "passive"))
      (node (ref "C144") (pin "1") (pinfunction "1_1") (pintype "passive"))
      (node (ref "C145") (pin "1") (pinfunction "1_1") (pintype "passive"))
      (node (ref "C146") (pin "1") (pinfunction "1_1") (pintype "passive"))
      (node (ref "C147") (pin "1") (pinfunction "1_1") (pintype "passive"))
      (node (ref "C148") (pin "1") (pinfunction "1_1") (pintype "passive"))
      (node (ref "C149") (pin "1") (pinfunction "1_1") (pintype "passive"))
      (node (ref "C150") (pin "1") (pinfunction "1_1") (pintype "passive"))
      (node (ref "C151") (pin "1") (pinfunction "1_1") (pintype "passive"))
      (node (ref "C152") (pin "1") (pinfunction "1_1") (pintype "passive"))
      (node (ref "C153") (pin "1") (pinfunction "1_1") (pintype "passive"))
      (node (ref "C154") (pin "1") (pinfunction "1_1") (pintype "passive"))
      (node (ref "C155") (pin "1") (pinfunction "1_1") (pintype "passive"))
      (node (ref "C156") (pin "1") (pinfunction "1_1") (pintype "passive"))
      (node (ref "C158") (pin "1") (pinfunction "1_1") (pintype "passive"))
      (node (ref "C160") (pin "1") (pinfunction "1_1") (pintype "passive"))
      (node (ref "C162") (pin "1") (pinfunction "1_1") (pintype "passive"))
      (node (ref "C198") (pin "1") (pinfunction "1_1") (pintype "passive"))
      (node (ref "C199") (pin "1") (pinfunction "1_1") (pintype "passive"))
      (node (ref "C204") (pin "1") (pinfunction "1_1") (pintype "passive"))
      (node (ref "C205") (pin "1") (pinfunction "1_1") (pintype "passive"))
      (node (ref "C206") (pin "1") (pinfunction "1_1") (pintype "passive"))
      (node (ref "C207") (pin "1") (pinfunction "1_1") (pintype "passive"))
      (node (ref "C208") (pin "1") (pinfunction "1_1") (pintype "passive"))
      (node (ref "C209") (pin "1") (pinfunction "1_1") (pintype "passive"))
      (node (ref "C210") (pin "1") (pinfunction "1_1") (pintype "passive"))
      (node (ref "C211") (pin "1") (pinfunction "1_1") (pintype "passive"))
      (node (ref "C212") (pin "1") (pinfunction "1_1") (pintype "passive"))
      (node (ref "C213") (pin "1") (pinfunction "1_1") (pintype "passive"))
      (node (ref "C214") (pin "1") (pinfunction "1_1") (pintype "passive"))
      (node (ref "C215") (pin "1") (pinfunction "1_1") (pintype "passive"))
      (node (ref "C216") (pin "1") (pinfunction "1_1") (pintype "passive"))
      (node (ref "C217") (pin "1") (pinfunction "1_1") (pintype "passive"))
      (node (ref "C38") (pin "1") (pinfunction "1_1") (pintype "passive"))
      (node (ref "C51") (pin "1") (pinfunction "1_1") (pintype "passive"))
      (node (ref "C52") (pin "1") (pinfunction "1_1") (pintype "passive"))
      (node (ref "C54") (pin "1") (pinfunction "1_1") (pintype "passive"))
      (node (ref "C55") (pin "1") (pinfunction "1_1") (pintype "passive"))
      (node (ref "C56") (pin "1") (pinfunction "1_1") (pintype "passive"))
      (node (ref "C57") (pin "1") (pinfunction "1_1") (pintype "passive"))
      (node (ref "C58") (pin "1") (pinfunction "1_1") (pintype "passive"))
      (node (ref "C59") (pin "1") (pinfunction "1_1") (pintype "passive"))
      (node (ref "C60") (pin "1") (pinfunction "1_1") (pintype "passive"))
      (node (ref "C63") (pin "1") (pinfunction "1_1") (pintype "passive"))
      (node (ref "C64") (pin "1") (pinfunction "1_1") (pintype "passive"))
      (node (ref "C65") (pin "1") (pinfunction "1_1") (pintype "passive"))
      (node (ref "C95") (pin "1") (pinfunction "1_1") (pintype "passive"))
      (node (ref "C98") (pin "1") (pinfunction "1_1") (pintype "passive"))
    )
    (net (code "2") (name "PA_GND") (class "Default")
      (node (ref "C161") (pin "1") (pinfunction "1_1") (pintype "passive"))
      (node (ref "C163") (pin "1") (pinfunction "1_1") (pintype "passive"))
      (node (ref "C164") (pin "1") (pinfunction "1_1") (pintype "passive"))
      (node (ref "C165") (pin "1") (pinfunction "1_1") (pintype "passive"))
      (node (ref "C166") (pin "1") (pinfunction "1_1") (pintype "passive"))
      (node (ref "C167") (pin "1") (pinfunction "1_1") (pintype "passive"))
      (node (ref "C168") (pin "1") (pinfunction "1_1") (pintype "passive"))
      (node (ref "C169") (pin "1") (pinfunction "1_1") (pintype "passive"))
      (node (ref "C170") (pin "1") (pinfunction "1_1") (pintype "passive"))
      (node (ref "C171") (pin "1") (pinfunction "1_1") (pintype "passive"))
      (node (ref "C172") (pin "1") (pinfunction "1_1") (pintype "passive"))
      (node (ref "C173") (pin "1") (pinfunction "1_1") (pintype "passive"))
      (node (ref "C174") (pin "1") (pinfunction "1_1") (pintype "passive"))
      (node (ref "C175") (pin "1") (pinfunction "1_1") (pintype "passive"))
      (node (ref "C176") (pin "1") (pinfunction "1_1") (pintype "passive"))
      (node (ref "C177") (pin "1") (pinfunction "1_1") (pintype "passive"))
      (node (ref "C178") (pin "1") (pinfunction "1_1") (pintype "passive"))
      (node (ref "C179") (pin "1") (pinfunction "1_1") (pintype "passive"))
      (node (ref "C180") (pin "1") (pinfunction "1_1") (pintype "passive"))
      (node (ref "C181") (pin "1") (pinfunction "1_1") (pintype "passive"))
      (node (ref "C184") (pin "1") (pinfunction "1_1") (pintype "passive"))
      (node (ref "C185") (pin "1") (pinfunction "1_1") (pintype "passive"))
      (node (ref "C186") (pin "1") (pinfunction "1_1") (pintype "passive"))
      (node (ref "C187") (pin "1") (pinfunction "1_1") (pintype "passive"))
      (node (ref "C189") (pin "1") (pinfunction "1_1") (pintype "passive"))
      (node (ref "C190") (pin "1") (pinfunction "1_1") (pintype "passive"))
      (node (ref "C193") (pin "1") (pinfunction "1_1") (pintype "passive"))
      (node (ref "C194") (pin "1") (pinfunction "1_1") (pintype "passive"))
      (node (ref "C196") (pin "1") (pinfunction "1_1") (pintype "passive"))
      (node (ref "C218") (pin "1") (pinfunction "1_1") (pintype "passive"))
      (node (ref "C219") (pin "1") (pinfunction "1_1") (pintype "passive"))
      (node (ref "C38") (pin "2") (pinfunction "2_2") (pintype "passive"))
      (node (ref "C51") (pin "2") (pinfunction "2_2") (pintype "passive"))
      (node (ref "C52") (pin "2") (pinfunction "2_2") (pintype "passive"))
      (node (ref "C54") (pin "2") (pinfunction "2_2") (pintype "passive"))
      (node (ref "C55") (pin "2") (pinfunction "2_2") (pintype "passive"))
      (node (ref "C56") (pin "2") (pinfunction "2_2") (pintype "passive"))
      (node (ref "C57") (pin "2") (pinfunction "2_2") (pintype "passive"))
      (node (ref "C58") (pin "2") (pinfunction "2_2") (pintype "passive"))
      (node (ref "C59") (pin "2") (pinfunction "2_2") (pintype "passive"))
      (node (ref "C60") (pin "2") (pinfunction "2_2") (pintype "passive"))
      (node (ref "C63") (pin "2") (pinfunction "2_2") (pintype "passive"))
      (node (ref "C64") (pin "2") (pinfunction "2_2") (pintype "passive"))
      (node (ref "C65") (pin "2") (pinfunction "2_2") (pintype "passive"))
      (node (ref "C95") (pin "2") (pinfunction "2_2") (pintype "passive"))
      (node (ref "C98") (pin "2") (pinfunction "2_2") (pintype "passive"))
    )
    (net (code "3") (name "SH") (class "Default")
      (node (ref "C130") (pin "2") (pinfunction "2_2") (pintype "passive"))
      (node (ref "C131") (pin "2") (pinfunction "2_2") (pintype "passive"))
      (node (ref "C132") (pin "2") (pinfunction "2_2") (pintype "passive"))
      (node (ref "C133") (pin "2") (pinfunction "2_2") (pintype "passive"))
      (node (ref "C134") (pin "2") (pinfunction "2_2") (pintype "passive"))
      (node (ref "C136") (pin "2") (pinfunction "2_2") (pintype "passive"))
      (node (ref "C137") (pin "2") (pinfunction "2_2") (pintype "passive"))
      (node (ref "C138") (pin "2") (pinfunction "2_2") (pintype "passive"))
      (node (ref "C139") (pin "2") (pinfunction "2_2") (pintype "passive"))
      (node (ref "C140") (pin "2") (pinfunction "2_2") (pintype "passive"))
      (node (ref "C142") (pin "2") (pinfunction "2_2") (pintype "passive"))
      (node (ref "C143") (pin "2") (pinfunction "2_2") (pintype "passive"))
      (node (ref "C144") (pin "2") (pinfunction "2_2") (pintype "passive"))
      (node (ref "C145") (pin "2") (pinfunction "2_2") (pintype "passive"))
      (node (ref "C146") (pin "2") (pinfunction "2_2") (pintype "passive"))
      (node (ref "C147") (pin "2") (pinfunction "2_2") (pintype "passive"))
      (node (ref "C148") (pin "2") (pinfunction "2_2") (pintype "passive"))
      (node (ref "C149") (pin "2") (pinfunction "2_2") (pintype "passive"))
      (node (ref "C150") (pin "2") (pinfunction "2_2") (pintype "passive"))
      (node (ref "C151") (pin "2") (pinfunction "2_2") (pintype "passive"))
      (node (ref "C152") (pin "2") (pinfunction "2_2") (pintype "passive"))
      (node (ref "C153") (pin "2") (pinfunction "2_2") (pintype "passive"))
      (node (ref "C154") (pin "2") (pinfunction "2_2") (pintype "passive"))
      (node (ref "C155") (pin "2") (pinfunction "2_2") (pintype "passive"))
      (node (ref "C156") (pin "2") (pinfunction "2_2") (pintype "passive"))
      (node (ref "C158") (pin "2") (pinfunction "2_2") (pintype "passive"))
      (node (ref "C160") (pin "2") (pinfunction "2_2") (pintype "passive"))
      (node (ref "C161") (pin "2") (pinfunction "2_2") (pintype "passive"))
      (node (ref "C162") (pin "2") (pinfunction "2_2") (pintype "passive"))
      (node (ref "C163") (pin "2") (pinfunction "2_2") (pintype "passive"))
      (node (ref "C164") (pin "2") (pinfunction "2_2") (pintype "passive"))
      (node (ref "C165") (pin "2") (pinfunction "2_2") (pintype "passive"))
      (node (ref "C166") (pin "2") (pinfunction "2_2") (pintype "passive"))
      (node (ref "C167") (pin "2") (pinfunction "2_2") (pintype "passive"))
      (node (ref "C168") (pin "2") (pinfunction "2_2") (pintype "passive"))
      (node (ref "C169") (pin "2") (pinfunction "2_2") (pintype "passive"))
      (node (ref "C170") (pin "2") (pinfunction "2_2") (pintype "passive"))
      (node (ref "C171") (pin "2") (pinfunction "2_2") (pintype "passive"))
      (node (ref "C172") (pin "2") (pinfunction "2_2") (pintype "passive"))
      (node (ref "C173") (pin "2") (pinfunction "2_2") (pintype "passive"))
      (node (ref "C174") (pin "2") (pinfunction "2_2") (pintype "passive"))
      (node (ref "C175") (pin "2") (pinfunction "2_2") (pintype "passive"))
      (node (ref "C176") (pin "2") (pinfunction "2_2") (pintype "passive"))
      (node (ref "C177") (pin "2") (pinfunction "2_2") (pintype "passive"))
      (node (ref "C178") (pin "2") (pinfunction "2_2") (pintype "passive"))
      (node (ref "C179") (pin "2") (pinfunction "2_2") (pintype "passive"))
      (node (ref "C180") (pin "2") (pinfunction "2_2") (pintype "passive"))
      (node (ref "C181") (pin "2") (pinfunction "2_2") (pintype "passive"))
      (node (ref "C184") (pin "2") (pinfunction "2_2") (pintype "passive"))
      (node (ref "C185") (pin "2") (pinfunction "2_2") (pintype "passive"))
      (node (ref "C186") (pin "2") (pinfunction "2_2") (pintype "passive"))
      (node (ref "C187") (pin "2") (pinfunction "2_2") (pintype "passive"))
      (node (ref "C189") (pin "2") (pinfunction "2_2") (pintype "passive"))
      (node (ref "C190") (pin "2") (pinfunction "2_2") (pintype "passive"))
      (node (ref "C193") (pin "2") (pinfunction "2_2") (pintype "passive"))
      (node (ref "C194") (pin "2") (pinfunction "2_2") (pintype "passive"))
      (node (ref "C196") (pin "2") (pinfunction "2_2") (pintype "passive"))
      (node (ref "C198") (pin "2") (pinfunction "2_2") (pintype "passive"))
      (node (ref "C199") (pin "2") (pinfunction "2_2") (pintype "passive"))
      (node (ref "C204") (pin "2") (pinfunction "2_2") (pintype "passive"))
      (node (ref "C205") (pin "2") (pinfunction "2_2") (pintype "passive"))
      (node (ref "C206") (pin "2") (pinfunction "2_2") (pintype "passive"))
      (node (ref "C207") (pin "2") (pinfunction "2_2") (pintype "passive"))
      (node (ref "C208") (pin "2") (pinfunction "2_2") (pintype "passive"))
      (node (ref "C209") (pin "2") (pinfunction "2_2") (pintype "passive"))
      (node (ref "C210") (pin "2") (pinfunction "2_2") (pintype "passive"))
      (node (ref "C211") (pin "2") (pinfunction "2_2") (pintype "passive"))
      (node (ref "C212") (pin "2") (pinfunction "2_2") (pintype "passive"))
      (node (ref "C213") (pin "2") (pinfunction "2_2") (pintype "passive"))
      (node (ref "C214") (pin "2") (pinfunction "2_2") (pintype "passive"))
      (node (ref "C215") (pin "2") (pinfunction "2_2") (pintype "passive"))
      (node (ref "C216") (pin "2") (pinfunction "2_2") (pintype "passive"))
      (node (ref "C217") (pin "2") (pinfunction "2_2") (pintype "passive"))
      (node (ref "C218") (pin "2") (pinfunction "2_2") (pintype "passive"))
      (node (ref "C219") (pin "2") (pinfunction "2_2") (pintype "passive"))
    )
  )
)
